# LEDs.net
KiCad netlist of a schematic drawn in Altium Designer
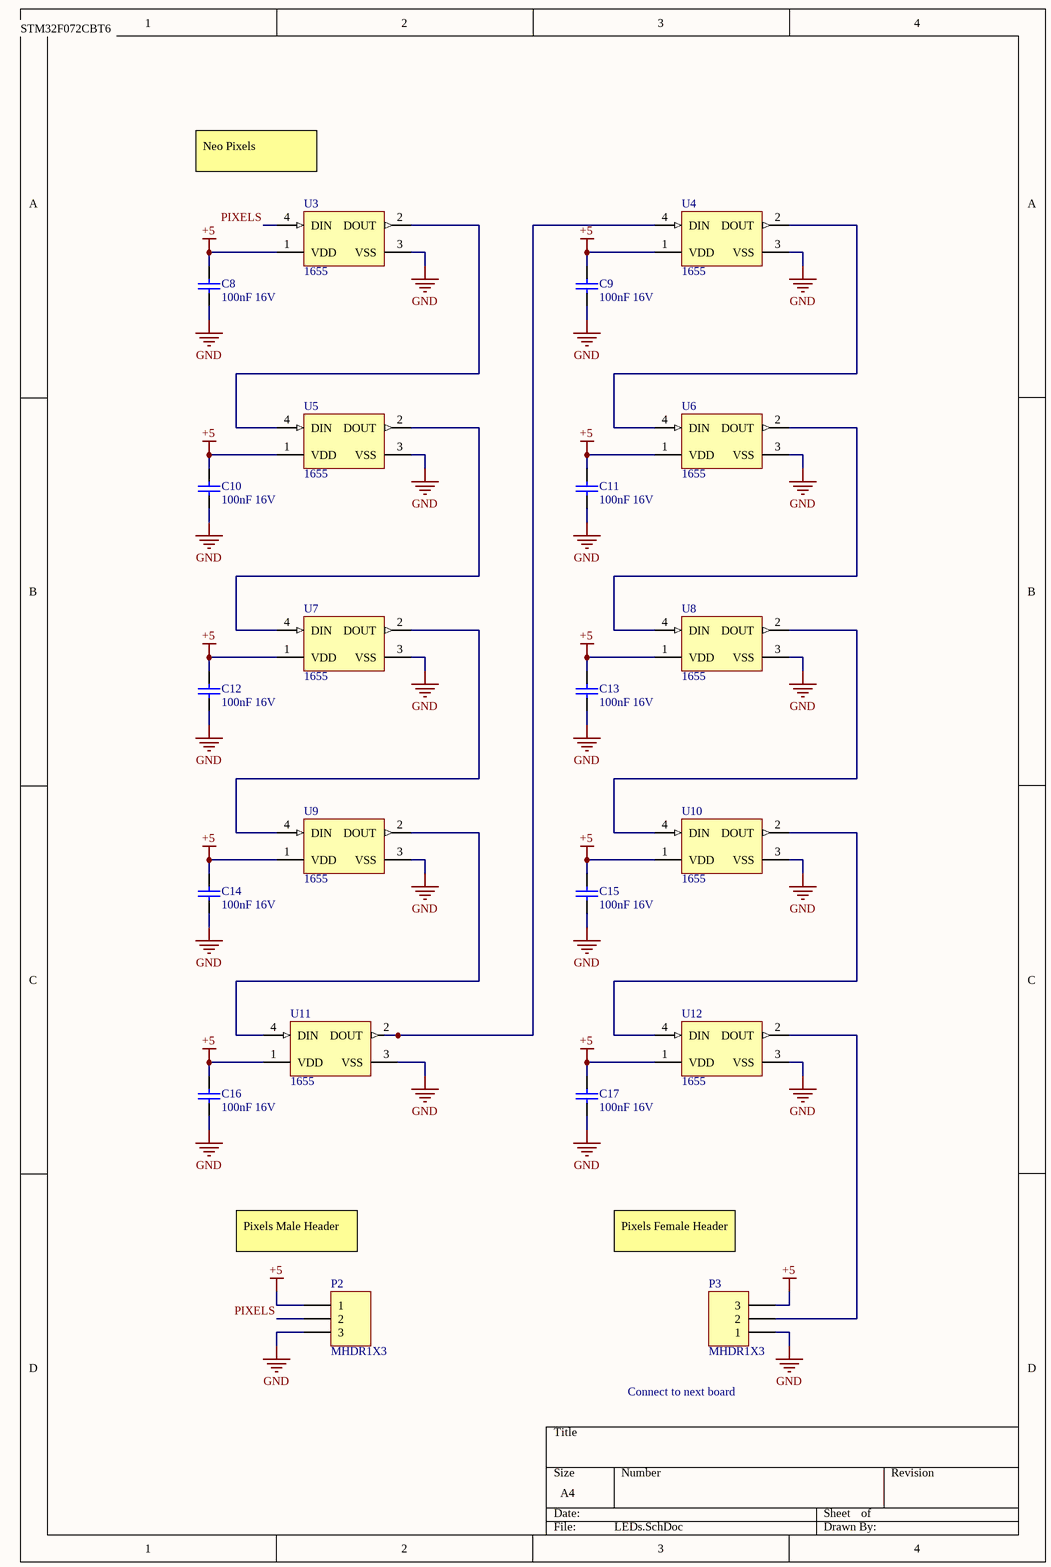
[diagram p0: LEDs.SchDoc]

(export (version "E")
  (design (tool "Eeschema 10.0.6"))
  (components
    (comp (ref "C8")
      (value "100nF 16V")
      (footprint "CAPC0603(1608)100_N")
      (description "CAP 100nF 16V ±10% 0603 (1608 Metric) Thickness 1mm SMD")
      (fields (field (name "TOLERANCE") "Â±10%"))
      (libsource (lib "Altium Content Vault") (part "CAP"))
    )
    (comp (ref "C9")
      (value "100nF 16V")
      (footprint "CAPC0603(1608)100_N")
      (description "CAP 100nF 16V ±10% 0603 (1608 Metric) Thickness 1mm SMD")
      (fields (field (name "TOLERANCE") "Â±10%"))
      (libsource (lib "Altium Content Vault") (part "CAP"))
    )
    (comp (ref "C10")
      (value "100nF 16V")
      (footprint "CAPC0603(1608)100_N")
      (description "CAP 100nF 16V ±10% 0603 (1608 Metric) Thickness 1mm SMD")
      (fields (field (name "TOLERANCE") "Â±10%"))
      (libsource (lib "Altium Content Vault") (part "CAP"))
    )
    (comp (ref "C11")
      (value "100nF 16V")
      (footprint "CAPC0603(1608)100_N")
      (description "CAP 100nF 16V ±10% 0603 (1608 Metric) Thickness 1mm SMD")
      (fields (field (name "TOLERANCE") "Â±10%"))
      (libsource (lib "Altium Content Vault") (part "CAP"))
    )
    (comp (ref "C12")
      (value "100nF 16V")
      (footprint "CAPC0603(1608)100_N")
      (description "CAP 100nF 16V ±10% 0603 (1608 Metric) Thickness 1mm SMD")
      (fields (field (name "TOLERANCE") "Â±10%"))
      (libsource (lib "Altium Content Vault") (part "CAP"))
    )
    (comp (ref "C13")
      (value "100nF 16V")
      (footprint "CAPC0603(1608)100_N")
      (description "CAP 100nF 16V ±10% 0603 (1608 Metric) Thickness 1mm SMD")
      (fields (field (name "TOLERANCE") "Â±10%"))
      (libsource (lib "Altium Content Vault") (part "CAP"))
    )
    (comp (ref "C14")
      (value "100nF 16V")
      (footprint "CAPC0603(1608)100_N")
      (description "CAP 100nF 16V ±10% 0603 (1608 Metric) Thickness 1mm SMD")
      (fields (field (name "TOLERANCE") "Â±10%"))
      (libsource (lib "Altium Content Vault") (part "CAP"))
    )
    (comp (ref "C15")
      (value "100nF 16V")
      (footprint "CAPC0603(1608)100_N")
      (description "CAP 100nF 16V ±10% 0603 (1608 Metric) Thickness 1mm SMD")
      (fields (field (name "TOLERANCE") "Â±10%"))
      (libsource (lib "Altium Content Vault") (part "CAP"))
    )
    (comp (ref "C16")
      (value "100nF 16V")
      (footprint "CAPC0603(1608)100_N")
      (description "CAP 100nF 16V ±10% 0603 (1608 Metric) Thickness 1mm SMD")
      (fields (field (name "TOLERANCE") "Â±10%"))
      (libsource (lib "Altium Content Vault") (part "CAP"))
    )
    (comp (ref "C17")
      (value "100nF 16V")
      (footprint "CAPC0603(1608)100_N")
      (description "CAP 100nF 16V ±10% 0603 (1608 Metric) Thickness 1mm SMD")
      (fields (field (name "TOLERANCE") "Â±10%"))
      (libsource (lib "Altium Content Vault") (part "CAP"))
    )
    (comp (ref "P2")
      (value "MHDR1X3")
      (footprint "MHDR1X3")
      (description "Header, 3-Pin")
      (fields (field (name "PUBLISHER") "Altium Limited"))
      (libsource (lib "") (part "MHDR1X3_1"))
    )
    (comp (ref "P3")
      (value "MHDR1X3")
      (footprint "MHDR1X3")
      (description "Header, 3-Pin")
      (fields (field (name "PUBLISHER") "Altium Limited"))
      (libsource (lib "Miscellaneous Connectors") (part "MHDR1X3"))
    )
    (comp (ref "U3")
      (value "1655")
      (footprint "ADA-RGB-1655_V")
      (fields (field (name "MANUFACTURER") "Adafruit-Industries-LLC"))
      (libsource (lib "Altium Content Vault") (part "ADA-RGB-1655-4"))
    )
    (comp (ref "U4")
      (value "1655")
      (footprint "ADA-RGB-1655_V")
      (fields (field (name "MANUFACTURER") "Adafruit-Industries-LLC"))
      (libsource (lib "Altium Content Vault") (part "ADA-RGB-1655-4"))
    )
    (comp (ref "U5")
      (value "1655")
      (footprint "ADA-RGB-1655_V")
      (fields (field (name "MANUFACTURER") "Adafruit-Industries-LLC"))
      (libsource (lib "Altium Content Vault") (part "ADA-RGB-1655-4"))
    )
    (comp (ref "U6")
      (value "1655")
      (footprint "ADA-RGB-1655_V")
      (fields (field (name "MANUFACTURER") "Adafruit-Industries-LLC"))
      (libsource (lib "Altium Content Vault") (part "ADA-RGB-1655-4"))
    )
    (comp (ref "U7")
      (value "1655")
      (footprint "ADA-RGB-1655_V")
      (fields (field (name "MANUFACTURER") "Adafruit-Industries-LLC"))
      (libsource (lib "Altium Content Vault") (part "ADA-RGB-1655-4"))
    )
    (comp (ref "U8")
      (value "1655")
      (footprint "ADA-RGB-1655_V")
      (fields (field (name "MANUFACTURER") "Adafruit-Industries-LLC"))
      (libsource (lib "Altium Content Vault") (part "ADA-RGB-1655-4"))
    )
    (comp (ref "U9")
      (value "1655")
      (footprint "ADA-RGB-1655_V")
      (fields (field (name "MANUFACTURER") "Adafruit-Industries-LLC"))
      (libsource (lib "Altium Content Vault") (part "ADA-RGB-1655-4"))
    )
    (comp (ref "U10")
      (value "1655")
      (footprint "ADA-RGB-1655_V")
      (fields (field (name "MANUFACTURER") "Adafruit-Industries-LLC"))
      (libsource (lib "Altium Content Vault") (part "ADA-RGB-1655-4"))
    )
    (comp (ref "U11")
      (value "1655")
      (footprint "ADA-RGB-1655_V")
      (fields (field (name "MANUFACTURER") "Adafruit-Industries-LLC"))
      (libsource (lib "Altium Content Vault") (part "ADA-RGB-1655-4"))
    )
    (comp (ref "U12")
      (value "1655")
      (footprint "ADA-RGB-1655_V")
      (fields (field (name "MANUFACTURER") "Adafruit-Industries-LLC"))
      (libsource (lib "Altium Content Vault") (part "ADA-RGB-1655-4"))
    )
  )
  (nets
    (net (code "1") (name "+5") (class "Default")
      (node (ref "C10") (pin "2") (pinfunction "2_2") (pintype "passive"))
      (node (ref "C11") (pin "2") (pinfunction "2_2") (pintype "passive"))
      (node (ref "C12") (pin "2") (pinfunction "2_2") (pintype "passive"))
      (node (ref "C13") (pin "2") (pinfunction "2_2") (pintype "passive"))
      (node (ref "C14") (pin "2") (pinfunction "2_2") (pintype "passive"))
      (node (ref "C15") (pin "2") (pinfunction "2_2") (pintype "passive"))
      (node (ref "C16") (pin "2") (pinfunction "2_2") (pintype "passive"))
      (node (ref "C17") (pin "2") (pinfunction "2_2") (pintype "passive"))
      (node (ref "C8") (pin "2") (pinfunction "2_2") (pintype "passive"))
      (node (ref "C9") (pin "2") (pinfunction "2_2") (pintype "passive"))
      (node (ref "P2") (pin "1") (pinfunction "1_1") (pintype "passive"))
      (node (ref "P3") (pin "3") (pinfunction "3_3") (pintype "passive"))
      (node (ref "U10") (pin "1") (pinfunction "VDD_1") (pintype "power_in"))
      (node (ref "U11") (pin "1") (pinfunction "VDD_1") (pintype "power_in"))
      (node (ref "U12") (pin "1") (pinfunction "VDD_1") (pintype "power_in"))
      (node (ref "U3") (pin "1") (pinfunction "VDD_1") (pintype "power_in"))
      (node (ref "U4") (pin "1") (pinfunction "VDD_1") (pintype "power_in"))
      (node (ref "U5") (pin "1") (pinfunction "VDD_1") (pintype "power_in"))
      (node (ref "U6") (pin "1") (pinfunction "VDD_1") (pintype "power_in"))
      (node (ref "U7") (pin "1") (pinfunction "VDD_1") (pintype "power_in"))
      (node (ref "U8") (pin "1") (pinfunction "VDD_1") (pintype "power_in"))
      (node (ref "U9") (pin "1") (pinfunction "VDD_1") (pintype "power_in"))
    )
    (net (code "2") (name "/PIXELS") (class "Default")
      (node (ref "P2") (pin "2") (pinfunction "2_2") (pintype "passive"))
      (node (ref "U3") (pin "4") (pinfunction "DIN_4") (pintype "input"))
    )
    (net (code "3") (name "GND") (class "Default")
      (node (ref "C10") (pin "1") (pinfunction "1_1") (pintype "passive"))
      (node (ref "C11") (pin "1") (pinfunction "1_1") (pintype "passive"))
      (node (ref "C12") (pin "1") (pinfunction "1_1") (pintype "passive"))
      (node (ref "C13") (pin "1") (pinfunction "1_1") (pintype "passive"))
      (node (ref "C14") (pin "1") (pinfunction "1_1") (pintype "passive"))
      (node (ref "C15") (pin "1") (pinfunction "1_1") (pintype "passive"))
      (node (ref "C16") (pin "1") (pinfunction "1_1") (pintype "passive"))
      (node (ref "C17") (pin "1") (pinfunction "1_1") (pintype "passive"))
      (node (ref "C8") (pin "1") (pinfunction "1_1") (pintype "passive"))
      (node (ref "C9") (pin "1") (pinfunction "1_1") (pintype "passive"))
      (node (ref "P2") (pin "3") (pinfunction "3_3") (pintype "passive"))
      (node (ref "P3") (pin "1") (pinfunction "1_1") (pintype "passive"))
      (node (ref "U10") (pin "3") (pinfunction "VSS_3") (pintype "power_in"))
      (node (ref "U11") (pin "3") (pinfunction "VSS_3") (pintype "power_in"))
      (node (ref "U12") (pin "3") (pinfunction "VSS_3") (pintype "power_in"))
      (node (ref "U3") (pin "3") (pinfunction "VSS_3") (pintype "power_in"))
      (node (ref "U4") (pin "3") (pinfunction "VSS_3") (pintype "power_in"))
      (node (ref "U5") (pin "3") (pinfunction "VSS_3") (pintype "power_in"))
      (node (ref "U6") (pin "3") (pinfunction "VSS_3") (pintype "power_in"))
      (node (ref "U7") (pin "3") (pinfunction "VSS_3") (pintype "power_in"))
      (node (ref "U8") (pin "3") (pinfunction "VSS_3") (pintype "power_in"))
      (node (ref "U9") (pin "3") (pinfunction "VSS_3") (pintype "power_in"))
    )
    (net (code "4") (name "Net-(U3-DOUT)") (class "Default")
      (node (ref "U3") (pin "2") (pinfunction "DOUT_2") (pintype "output"))
      (node (ref "U5") (pin "4") (pinfunction "DIN_4") (pintype "input"))
    )
    (net (code "5") (name "Net-(U4-DOUT)") (class "Default")
      (node (ref "U4") (pin "2") (pinfunction "DOUT_2") (pintype "output"))
      (node (ref "U6") (pin "4") (pinfunction "DIN_4") (pintype "input"))
    )
    (net (code "6") (name "Net-(U5-DOUT)") (class "Default")
      (node (ref "U5") (pin "2") (pinfunction "DOUT_2") (pintype "output"))
      (node (ref "U7") (pin "4") (pinfunction "DIN_4") (pintype "input"))
    )
    (net (code "7") (name "Net-(U6-DOUT)") (class "Default")
      (node (ref "U6") (pin "2") (pinfunction "DOUT_2") (pintype "output"))
      (node (ref "U8") (pin "4") (pinfunction "DIN_4") (pintype "input"))
    )
    (net (code "8") (name "Net-(U7-DOUT)") (class "Default")
      (node (ref "U7") (pin "2") (pinfunction "DOUT_2") (pintype "output"))
      (node (ref "U9") (pin "4") (pinfunction "DIN_4") (pintype "input"))
    )
    (net (code "9") (name "Net-(U10-DIN)") (class "Default")
      (node (ref "U10") (pin "4") (pinfunction "DIN_4") (pintype "input"))
      (node (ref "U8") (pin "2") (pinfunction "DOUT_2") (pintype "output"))
    )
    (net (code "10") (name "Net-(U10-DOUT)") (class "Default")
      (node (ref "U10") (pin "2") (pinfunction "DOUT_2") (pintype "output"))
      (node (ref "U12") (pin "4") (pinfunction "DIN_4") (pintype "input"))
    )
    (net (code "11") (name "Net-(U11-DIN)") (class "Default")
      (node (ref "U11") (pin "4") (pinfunction "DIN_4") (pintype "input"))
      (node (ref "U9") (pin "2") (pinfunction "DOUT_2") (pintype "output"))
    )
    (net (code "12") (name "Net-(U11-DOUT)") (class "Default")
      (node (ref "U11") (pin "2") (pinfunction "DOUT_2") (pintype "output"))
      (node (ref "U4") (pin "4") (pinfunction "DIN_4") (pintype "input"))
    )
    (net (code "13") (name "Net-(U12-DOUT)") (class "Default")
      (node (ref "P3") (pin "2") (pinfunction "2_2") (pintype "passive"))
      (node (ref "U12") (pin "2") (pinfunction "DOUT_2") (pintype "output"))
    )
  )
)
